# MLX90393_breakout1_short2.net
KiCad netlist of a schematic drawn in EAGLE
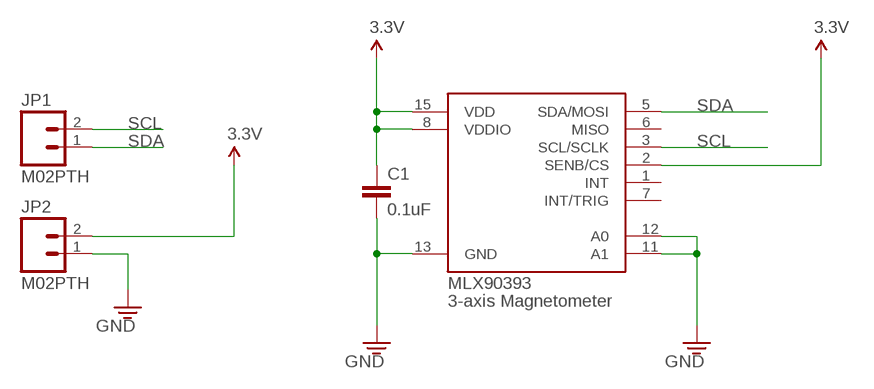
[diagram p0: schematic, sheet 1]

(export (version "E")
  (design (tool "Eeschema 10.0.6"))
  (components
    (comp (ref "C1")
      (value "0.1uF")
      (footprint "eagle-import:0603")
      (libsource (lib "eagle-import") (part "CAP0603"))
    )
    (comp (ref "JP1")
      (value "M02PTH")
      (footprint "eagle-import:1X02")
      (libsource (lib "eagle-import") (part "M02PTH"))
    )
    (comp (ref "JP2")
      (value "M02PTH")
      (footprint "eagle-import:1X02")
      (libsource (lib "eagle-import") (part "M02PTH"))
    )
    (comp (ref "U$1")
      (value "MLX90393")
      (footprint "eagle-import:16-QFN")
      (libsource (lib "eagle-import") (part "MLX90393"))
    )
  )
  (nets
    (net (code "1") (name "/SCL") (class "Default")
      (node (ref "JP1") (pin "2") (pinfunction "2_2") (pintype "passive"))
      (node (ref "U$1") (pin "3") (pinfunction "SCL/SCLK_3") (pintype "bidirectional"))
    )
    (net (code "2") (name "/SDA") (class "Default")
      (node (ref "JP1") (pin "1") (pinfunction "1_1") (pintype "passive"))
      (node (ref "U$1") (pin "5") (pinfunction "SDA/MOSI_5") (pintype "bidirectional"))
    )
    (net (code "3") (name "3.3V") (class "Default")
      (node (ref "C1") (pin "1") (pinfunction "1_1") (pintype "passive"))
      (node (ref "JP2") (pin "2") (pinfunction "2_2") (pintype "passive"))
      (node (ref "U$1") (pin "15") (pinfunction "VDD_15") (pintype "bidirectional"))
      (node (ref "U$1") (pin "2") (pinfunction "SENB/CS_2") (pintype "bidirectional"))
      (node (ref "U$1") (pin "8") (pinfunction "VDDIO_8") (pintype "bidirectional"))
    )
    (net (code "4") (name "GND") (class "Default")
      (node (ref "C1") (pin "2") (pinfunction "2_2") (pintype "passive"))
      (node (ref "JP2") (pin "1") (pinfunction "1_1") (pintype "passive"))
      (node (ref "U$1") (pin "11") (pinfunction "A1_11") (pintype "bidirectional"))
      (node (ref "U$1") (pin "12") (pinfunction "A0_12") (pintype "bidirectional"))
      (node (ref "U$1") (pin "13") (pinfunction "GND_13") (pintype "bidirectional"))
    )
    (net (code "5") (name "unconnected-(U$1-INT-Pad1)") (class "Default")
      (node (ref "U$1") (pin "1") (pinfunction "INT_1") (pintype "bidirectional"))
    )
    (net (code "6") (name "unconnected-(U$1-INT{slash}TRIG-Pad7)") (class "Default")
      (node (ref "U$1") (pin "7") (pinfunction "INT/TRIG_7") (pintype "bidirectional"))
    )
    (net (code "7") (name "unconnected-(U$1-MISO-Pad6)") (class "Default")
      (node (ref "U$1") (pin "6") (pinfunction "MISO_6") (pintype "bidirectional"))
    )
  )
)
